# sense-amp.net
KiCad netlist of a schematic drawn in EAGLE
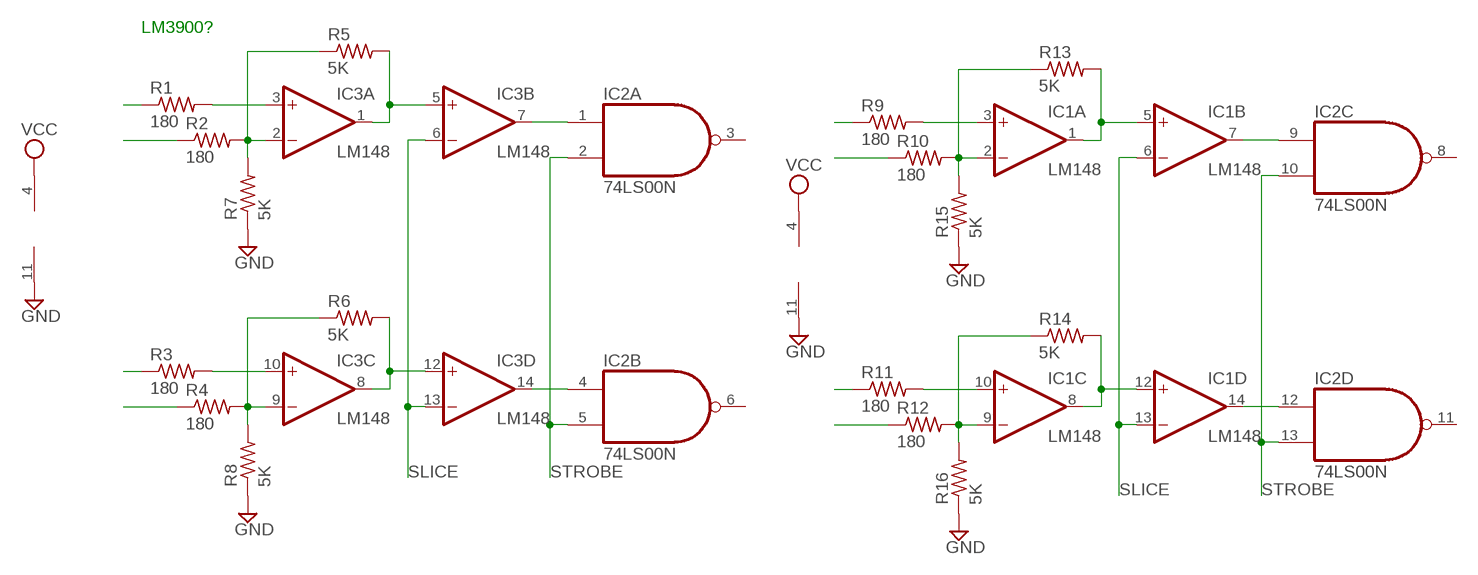
[diagram p0: schematic, sheet 1]

(export (version "E")
  (design (tool "Eeschema 10.0.6"))
  (components
    (comp (ref "IC1")
      (value "LM148")
      (footprint "eagle-import:DIL14")
      (libsource (lib "eagle-import") (part "OP11P"))
    )
    (comp (ref "IC2")
      (value "74LS00N")
      (footprint "eagle-import:DIL14")
      (libsource (lib "eagle-import") (part "7400NLS"))
    )
    (comp (ref "IC3")
      (value "LM148")
      (footprint "eagle-import:DIL14")
      (libsource (lib "eagle-import") (part "OP11P"))
    )
    (comp (ref "R1")
      (value "180")
      (footprint "eagle-import:0207_10")
      (libsource (lib "eagle-import") (part "R-US_0207/10"))
    )
    (comp (ref "R2")
      (value "180")
      (footprint "eagle-import:0207_10")
      (libsource (lib "eagle-import") (part "R-US_0207/10"))
    )
    (comp (ref "R3")
      (value "180")
      (footprint "eagle-import:0207_10")
      (libsource (lib "eagle-import") (part "R-US_0207/10"))
    )
    (comp (ref "R4")
      (value "180")
      (footprint "eagle-import:0207_10")
      (libsource (lib "eagle-import") (part "R-US_0207/10"))
    )
    (comp (ref "R5")
      (value "5K")
      (footprint "eagle-import:0207_10")
      (libsource (lib "eagle-import") (part "R-US_0207/10"))
    )
    (comp (ref "R6")
      (value "5K")
      (footprint "eagle-import:0207_10")
      (libsource (lib "eagle-import") (part "R-US_0207/10"))
    )
    (comp (ref "R7")
      (value "5K")
      (footprint "eagle-import:0207_10")
      (libsource (lib "eagle-import") (part "R-US_0207/10"))
    )
    (comp (ref "R8")
      (value "5K")
      (footprint "eagle-import:0207_10")
      (libsource (lib "eagle-import") (part "R-US_0207/10"))
    )
    (comp (ref "R9")
      (value "180")
      (footprint "eagle-import:0207_10")
      (libsource (lib "eagle-import") (part "R-US_0207/10"))
    )
    (comp (ref "R10")
      (value "180")
      (footprint "eagle-import:0207_10")
      (libsource (lib "eagle-import") (part "R-US_0207/10"))
    )
    (comp (ref "R11")
      (value "180")
      (footprint "eagle-import:0207_10")
      (libsource (lib "eagle-import") (part "R-US_0207/10"))
    )
    (comp (ref "R12")
      (value "180")
      (footprint "eagle-import:0207_10")
      (libsource (lib "eagle-import") (part "R-US_0207/10"))
    )
    (comp (ref "R13")
      (value "5K")
      (footprint "eagle-import:0207_10")
      (libsource (lib "eagle-import") (part "R-US_0207/10"))
    )
    (comp (ref "R14")
      (value "5K")
      (footprint "eagle-import:0207_10")
      (libsource (lib "eagle-import") (part "R-US_0207/10"))
    )
    (comp (ref "R15")
      (value "5K")
      (footprint "eagle-import:0207_10")
      (libsource (lib "eagle-import") (part "R-US_0207/10"))
    )
    (comp (ref "R16")
      (value "5K")
      (footprint "eagle-import:0207_10")
      (libsource (lib "eagle-import") (part "R-US_0207/10"))
    )
  )
  (nets
    (net (code "1") (name "/SLICE") (class "Default")
      (node (ref "IC1") (pin "13") (pinfunction "-IN_13") (pintype "input"))
      (node (ref "IC1") (pin "6") (pinfunction "-IN_6") (pintype "input"))
      (node (ref "IC3") (pin "13") (pinfunction "-IN_13") (pintype "input"))
      (node (ref "IC3") (pin "6") (pinfunction "-IN_6") (pintype "input"))
    )
    (net (code "2") (name "/STROBE") (class "Default")
      (node (ref "IC2") (pin "10") (pinfunction "I1_10") (pintype "input"))
      (node (ref "IC2") (pin "13") (pinfunction "I1_13") (pintype "input"))
      (node (ref "IC2") (pin "2") (pinfunction "I1_2") (pintype "input"))
      (node (ref "IC2") (pin "5") (pinfunction "I1_5") (pintype "input"))
    )
    (net (code "3") (name "GND") (class "Default")
      (node (ref "IC1") (pin "11") (pinfunction "V-_11") (pintype "power_in"))
      (node (ref "IC3") (pin "11") (pinfunction "V-_11") (pintype "power_in"))
      (node (ref "R15") (pin "1") (pinfunction "1_1") (pintype "passive"))
      (node (ref "R16") (pin "1") (pinfunction "1_1") (pintype "passive"))
      (node (ref "R7") (pin "1") (pinfunction "1_1") (pintype "passive"))
      (node (ref "R8") (pin "1") (pinfunction "1_1") (pintype "passive"))
    )
    (net (code "4") (name "Net-(IC1A-+IN)") (class "Default")
      (node (ref "IC1") (pin "3") (pinfunction "+IN_3") (pintype "input"))
      (node (ref "R9") (pin "2") (pinfunction "2_2") (pintype "passive"))
    )
    (net (code "5") (name "Net-(IC1A--IN)") (class "Default")
      (node (ref "IC1") (pin "2") (pinfunction "-IN_2") (pintype "input"))
      (node (ref "R10") (pin "2") (pinfunction "2_2") (pintype "passive"))
      (node (ref "R13") (pin "1") (pinfunction "1_1") (pintype "passive"))
      (node (ref "R15") (pin "2") (pinfunction "2_2") (pintype "passive"))
    )
    (net (code "6") (name "Net-(IC1A-OUT)") (class "Default")
      (node (ref "IC1") (pin "1") (pinfunction "OUT_1") (pintype "output"))
      (node (ref "IC1") (pin "5") (pinfunction "+IN_5") (pintype "input"))
      (node (ref "R13") (pin "2") (pinfunction "2_2") (pintype "passive"))
    )
    (net (code "7") (name "Net-(IC1B-OUT)") (class "Default")
      (node (ref "IC1") (pin "7") (pinfunction "OUT_7") (pintype "output"))
      (node (ref "IC2") (pin "9") (pinfunction "I0_9") (pintype "input"))
    )
    (net (code "8") (name "Net-(IC1C-+IN)") (class "Default")
      (node (ref "IC1") (pin "10") (pinfunction "+IN_10") (pintype "input"))
      (node (ref "R11") (pin "2") (pinfunction "2_2") (pintype "passive"))
    )
    (net (code "9") (name "Net-(IC1C--IN)") (class "Default")
      (node (ref "IC1") (pin "9") (pinfunction "-IN_9") (pintype "input"))
      (node (ref "R12") (pin "2") (pinfunction "2_2") (pintype "passive"))
      (node (ref "R14") (pin "1") (pinfunction "1_1") (pintype "passive"))
      (node (ref "R16") (pin "2") (pinfunction "2_2") (pintype "passive"))
    )
    (net (code "10") (name "Net-(IC1C-OUT)") (class "Default")
      (node (ref "IC1") (pin "12") (pinfunction "+IN_12") (pintype "input"))
      (node (ref "IC1") (pin "8") (pinfunction "OUT_8") (pintype "output"))
      (node (ref "R14") (pin "2") (pinfunction "2_2") (pintype "passive"))
    )
    (net (code "11") (name "Net-(IC1D-OUT)") (class "Default")
      (node (ref "IC1") (pin "14") (pinfunction "OUT_14") (pintype "output"))
      (node (ref "IC2") (pin "12") (pinfunction "I0_12") (pintype "input"))
    )
    (net (code "12") (name "Net-(IC2A-I0)") (class "Default")
      (node (ref "IC2") (pin "1") (pinfunction "I0_1") (pintype "input"))
      (node (ref "IC3") (pin "7") (pinfunction "OUT_7") (pintype "output"))
    )
    (net (code "13") (name "Net-(IC2B-I0)") (class "Default")
      (node (ref "IC2") (pin "4") (pinfunction "I0_4") (pintype "input"))
      (node (ref "IC3") (pin "14") (pinfunction "OUT_14") (pintype "output"))
    )
    (net (code "14") (name "Net-(IC3A-+IN)") (class "Default")
      (node (ref "IC3") (pin "3") (pinfunction "+IN_3") (pintype "input"))
      (node (ref "R1") (pin "2") (pinfunction "2_2") (pintype "passive"))
    )
    (net (code "15") (name "Net-(IC3A--IN)") (class "Default")
      (node (ref "IC3") (pin "2") (pinfunction "-IN_2") (pintype "input"))
      (node (ref "R2") (pin "2") (pinfunction "2_2") (pintype "passive"))
      (node (ref "R5") (pin "1") (pinfunction "1_1") (pintype "passive"))
      (node (ref "R7") (pin "2") (pinfunction "2_2") (pintype "passive"))
    )
    (net (code "16") (name "Net-(IC3A-OUT)") (class "Default")
      (node (ref "IC3") (pin "1") (pinfunction "OUT_1") (pintype "output"))
      (node (ref "IC3") (pin "5") (pinfunction "+IN_5") (pintype "input"))
      (node (ref "R5") (pin "2") (pinfunction "2_2") (pintype "passive"))
    )
    (net (code "17") (name "Net-(IC3C-+IN)") (class "Default")
      (node (ref "IC3") (pin "10") (pinfunction "+IN_10") (pintype "input"))
      (node (ref "R3") (pin "2") (pinfunction "2_2") (pintype "passive"))
    )
    (net (code "18") (name "Net-(IC3C--IN)") (class "Default")
      (node (ref "IC3") (pin "9") (pinfunction "-IN_9") (pintype "input"))
      (node (ref "R4") (pin "2") (pinfunction "2_2") (pintype "passive"))
      (node (ref "R6") (pin "1") (pinfunction "1_1") (pintype "passive"))
      (node (ref "R8") (pin "2") (pinfunction "2_2") (pintype "passive"))
    )
    (net (code "19") (name "Net-(IC3C-OUT)") (class "Default")
      (node (ref "IC3") (pin "12") (pinfunction "+IN_12") (pintype "input"))
      (node (ref "IC3") (pin "8") (pinfunction "OUT_8") (pintype "output"))
      (node (ref "R6") (pin "2") (pinfunction "2_2") (pintype "passive"))
    )
    (net (code "20") (name "VCC") (class "Default")
      (node (ref "IC1") (pin "4") (pinfunction "V+_4") (pintype "power_in"))
      (node (ref "IC3") (pin "4") (pinfunction "V+_4") (pintype "power_in"))
    )
    (net (code "21") (name "unconnected-(IC2A-O-Pad3)") (class "Default")
      (node (ref "IC2") (pin "3") (pinfunction "O_3") (pintype "output"))
    )
    (net (code "22") (name "unconnected-(IC2B-O-Pad6)") (class "Default")
      (node (ref "IC2") (pin "6") (pinfunction "O_6") (pintype "output"))
    )
    (net (code "23") (name "unconnected-(IC2C-O-Pad8)") (class "Default")
      (node (ref "IC2") (pin "8") (pinfunction "O_8") (pintype "output"))
    )
    (net (code "24") (name "unconnected-(IC2D-O-Pad11)") (class "Default")
      (node (ref "IC2") (pin "11") (pinfunction "O_11") (pintype "output"))
    )
    (net (code "25") (name "unconnected-(R1-Pad1)") (class "Default")
      (node (ref "R1") (pin "1") (pinfunction "1_1") (pintype "passive"))
    )
    (net (code "26") (name "unconnected-(R2-Pad1)") (class "Default")
      (node (ref "R2") (pin "1") (pinfunction "1_1") (pintype "passive"))
    )
    (net (code "27") (name "unconnected-(R3-Pad1)") (class "Default")
      (node (ref "R3") (pin "1") (pinfunction "1_1") (pintype "passive"))
    )
    (net (code "28") (name "unconnected-(R4-Pad1)") (class "Default")
      (node (ref "R4") (pin "1") (pinfunction "1_1") (pintype "passive"))
    )
    (net (code "29") (name "unconnected-(R9-Pad1)") (class "Default")
      (node (ref "R9") (pin "1") (pinfunction "1_1") (pintype "passive"))
    )
    (net (code "30") (name "unconnected-(R10-Pad1)") (class "Default")
      (node (ref "R10") (pin "1") (pinfunction "1_1") (pintype "passive"))
    )
    (net (code "31") (name "unconnected-(R11-Pad1)") (class "Default")
      (node (ref "R11") (pin "1") (pinfunction "1_1") (pintype "passive"))
    )
    (net (code "32") (name "unconnected-(R12-Pad1)") (class "Default")
      (node (ref "R12") (pin "1") (pinfunction "1_1") (pintype "passive"))
    )
  )
)
